# luca.net
KiCad netlist of a schematic drawn in EAGLE
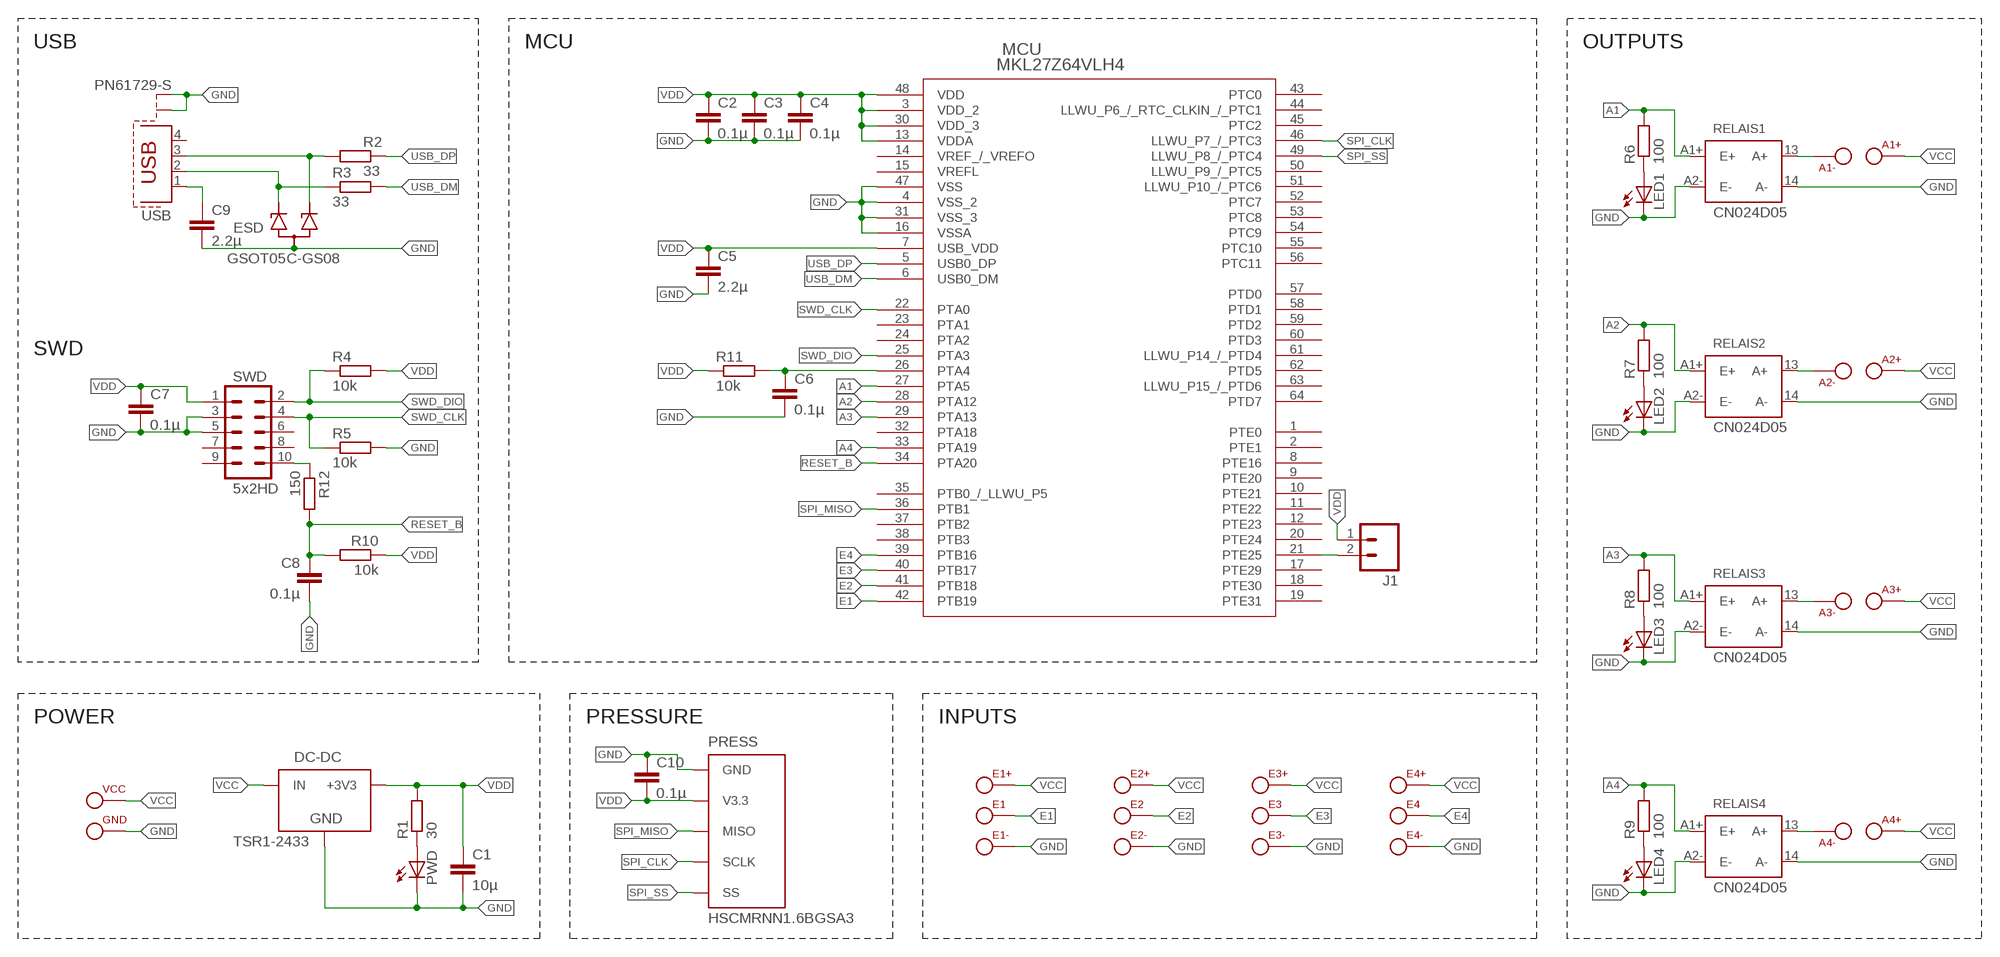
[diagram p0: schematic, sheet 1]

(export (version "E")
  (design (tool "Eeschema 10.0.6"))
  (components
    (comp (ref "A1+")
      (value "FFKDS-2,54")
      (footprint "eagle-import:FFSDK-2,54")
      (libsource (lib "eagle-import") (part "FFKDS-2,54"))
    )
    (comp (ref "A1-")
      (value "FFKDS-2,54")
      (footprint "eagle-import:FFSDK-2,54")
      (libsource (lib "eagle-import") (part "FFKDS-2,54"))
    )
    (comp (ref "A2+")
      (value "FFKDS-2,54")
      (footprint "eagle-import:FFSDK-2,54")
      (libsource (lib "eagle-import") (part "FFKDS-2,54"))
    )
    (comp (ref "A2-")
      (value "FFKDS-2,54")
      (footprint "eagle-import:FFSDK-2,54")
      (libsource (lib "eagle-import") (part "FFKDS-2,54"))
    )
    (comp (ref "A3+")
      (value "FFKDS-2,54")
      (footprint "eagle-import:FFSDK-2,54")
      (libsource (lib "eagle-import") (part "FFKDS-2,54"))
    )
    (comp (ref "A3-")
      (value "FFKDS-2,54")
      (footprint "eagle-import:FFSDK-2,54")
      (libsource (lib "eagle-import") (part "FFKDS-2,54"))
    )
    (comp (ref "A4+")
      (value "FFKDS-2,54")
      (footprint "eagle-import:FFSDK-2,54")
      (libsource (lib "eagle-import") (part "FFKDS-2,54"))
    )
    (comp (ref "A4-")
      (value "FFKDS-2,54")
      (footprint "eagle-import:FFSDK-2,54")
      (libsource (lib "eagle-import") (part "FFKDS-2,54"))
    )
    (comp (ref "C1")
      (value "10µ")
      (footprint "eagle-import:C1206")
      (libsource (lib "eagle-import") (part "C-EUC1206"))
    )
    (comp (ref "C2")
      (value "0.1µ")
      (footprint "eagle-import:C1206")
      (libsource (lib "eagle-import") (part "C-EUC1206"))
    )
    (comp (ref "C3")
      (value "0.1µ")
      (footprint "eagle-import:C1206")
      (libsource (lib "eagle-import") (part "C-EUC1206"))
    )
    (comp (ref "C4")
      (value "0.1µ")
      (footprint "eagle-import:C1206")
      (libsource (lib "eagle-import") (part "C-EUC1206"))
    )
    (comp (ref "C5")
      (value "2.2µ")
      (footprint "eagle-import:C1206")
      (libsource (lib "eagle-import") (part "C-EUC1206"))
    )
    (comp (ref "C6")
      (value "0.1µ")
      (footprint "eagle-import:C1206")
      (libsource (lib "eagle-import") (part "C-EUC1206"))
    )
    (comp (ref "C7")
      (value "0.1µ")
      (footprint "eagle-import:C1206")
      (libsource (lib "eagle-import") (part "C-EUC1206"))
    )
    (comp (ref "C8")
      (value "0.1µ")
      (footprint "eagle-import:C1206")
      (libsource (lib "eagle-import") (part "C-EUC1206"))
    )
    (comp (ref "C9")
      (value "2.2µ")
      (footprint "eagle-import:C1206")
      (libsource (lib "eagle-import") (part "C-EUC1206"))
    )
    (comp (ref "C10")
      (value "0.1µ")
      (footprint "eagle-import:C1206")
      (libsource (lib "eagle-import") (part "C-EUC1206"))
    )
    (comp (ref "DC-DC")
      (value "TSR1-2433")
      (footprint "eagle-import:TSR-1")
      (libsource (lib "eagle-import") (part "TSR1-2433"))
    )
    (comp (ref "E1")
      (value "FFKDS-2,54")
      (footprint "eagle-import:FFSDK-2,54")
      (libsource (lib "eagle-import") (part "FFKDS-2,54"))
    )
    (comp (ref "E1+")
      (value "FFKDS-2,54")
      (footprint "eagle-import:FFSDK-2,54")
      (libsource (lib "eagle-import") (part "FFKDS-2,54"))
    )
    (comp (ref "E1-")
      (value "FFKDS-2,54")
      (footprint "eagle-import:FFSDK-2,54")
      (libsource (lib "eagle-import") (part "FFKDS-2,54"))
    )
    (comp (ref "E2")
      (value "FFKDS-2,54")
      (footprint "eagle-import:FFSDK-2,54")
      (libsource (lib "eagle-import") (part "FFKDS-2,54"))
    )
    (comp (ref "E2+")
      (value "FFKDS-2,54")
      (footprint "eagle-import:FFSDK-2,54")
      (libsource (lib "eagle-import") (part "FFKDS-2,54"))
    )
    (comp (ref "E2-")
      (value "FFKDS-2,54")
      (footprint "eagle-import:FFSDK-2,54")
      (libsource (lib "eagle-import") (part "FFKDS-2,54"))
    )
    (comp (ref "E3")
      (value "FFKDS-2,54")
      (footprint "eagle-import:FFSDK-2,54")
      (libsource (lib "eagle-import") (part "FFKDS-2,54"))
    )
    (comp (ref "E3+")
      (value "FFKDS-2,54")
      (footprint "eagle-import:FFSDK-2,54")
      (libsource (lib "eagle-import") (part "FFKDS-2,54"))
    )
    (comp (ref "E3-")
      (value "FFKDS-2,54")
      (footprint "eagle-import:FFSDK-2,54")
      (libsource (lib "eagle-import") (part "FFKDS-2,54"))
    )
    (comp (ref "E4")
      (value "FFKDS-2,54")
      (footprint "eagle-import:FFSDK-2,54")
      (libsource (lib "eagle-import") (part "FFKDS-2,54"))
    )
    (comp (ref "E4+")
      (value "FFKDS-2,54")
      (footprint "eagle-import:FFSDK-2,54")
      (libsource (lib "eagle-import") (part "FFKDS-2,54"))
    )
    (comp (ref "E4-")
      (value "FFKDS-2,54")
      (footprint "eagle-import:FFSDK-2,54")
      (libsource (lib "eagle-import") (part "FFKDS-2,54"))
    )
    (comp (ref "ESD")
      (value "GSOT05C-GS08")
      (footprint "eagle-import:GSOT05C-GS08")
      (libsource (lib "eagle-import") (part "GSOT05C-GS08"))
    )
    (comp (ref "GND")
      (value "FFKDS-2,54")
      (footprint "eagle-import:FFSDK-2,54")
      (libsource (lib "eagle-import") (part "FFKDS-2,54"))
    )
    (comp (ref "J1")
      (value "M02LOCK")
      (footprint "eagle-import:1X02_LOCK")
      (libsource (lib "eagle-import") (part "M02LOCK"))
    )
    (comp (ref "LED1")
      (value "LED")
      (footprint "eagle-import:LED")
      (libsource (lib "eagle-import") (part "LED"))
    )
    (comp (ref "LED2")
      (value "LED")
      (footprint "eagle-import:LED")
      (libsource (lib "eagle-import") (part "LED"))
    )
    (comp (ref "LED3")
      (value "LED")
      (footprint "eagle-import:LED")
      (libsource (lib "eagle-import") (part "LED"))
    )
    (comp (ref "LED4")
      (value "LED")
      (footprint "eagle-import:LED")
      (libsource (lib "eagle-import") (part "LED"))
    )
    (comp (ref "MCU")
      (value "MKL27Z64VLH4")
      (footprint "eagle-import:98ASS23234W")
      (fields (field (name "MANUFACTURER_PART_NUMBER") "mkl27z64vlh4"))
      (libsource (lib "eagle-import") (part "MKL27Z64VLH4"))
    )
    (comp (ref "PRESS")
      (value "HSCMRNN1.6BGSA3")
      (footprint "eagle-import:HSCMRNN1.6BGSA3")
      (libsource (lib "eagle-import") (part "HSCMRNN1.6BGSA3"))
    )
    (comp (ref "PWD")
      (value "LED")
      (footprint "eagle-import:LED")
      (libsource (lib "eagle-import") (part "LED"))
    )
    (comp (ref "R1")
      (value "30")
      (footprint "eagle-import:M1206")
      (libsource (lib "eagle-import") (part "R-EU_M1206"))
    )
    (comp (ref "R2")
      (value "33")
      (footprint "eagle-import:M1206")
      (libsource (lib "eagle-import") (part "R-EU_M1206"))
    )
    (comp (ref "R3")
      (value "33")
      (footprint "eagle-import:M1206")
      (libsource (lib "eagle-import") (part "R-EU_M1206"))
    )
    (comp (ref "R4")
      (value "10k")
      (footprint "eagle-import:M1206")
      (libsource (lib "eagle-import") (part "R-EU_M1206"))
    )
    (comp (ref "R5")
      (value "10k")
      (footprint "eagle-import:M1206")
      (libsource (lib "eagle-import") (part "R-EU_M1206"))
    )
    (comp (ref "R6")
      (value "100")
      (footprint "eagle-import:M1206")
      (libsource (lib "eagle-import") (part "R-EU_M1206"))
    )
    (comp (ref "R7")
      (value "100")
      (footprint "eagle-import:M1206")
      (libsource (lib "eagle-import") (part "R-EU_M1206"))
    )
    (comp (ref "R8")
      (value "100")
      (footprint "eagle-import:M1206")
      (libsource (lib "eagle-import") (part "R-EU_M1206"))
    )
    (comp (ref "R9")
      (value "100")
      (footprint "eagle-import:M1206")
      (libsource (lib "eagle-import") (part "R-EU_M1206"))
    )
    (comp (ref "R10")
      (value "10k")
      (footprint "eagle-import:M1206")
      (libsource (lib "eagle-import") (part "R-EU_M1206"))
    )
    (comp (ref "R11")
      (value "10k")
      (footprint "eagle-import:M1206")
      (libsource (lib "eagle-import") (part "R-EU_M1206"))
    )
    (comp (ref "R12")
      (value "150")
      (footprint "eagle-import:M1206")
      (libsource (lib "eagle-import") (part "R-EU_M1206"))
    )
    (comp (ref "RELAIS1")
      (value "CN024D05")
      (footprint "eagle-import:CN024D05")
      (libsource (lib "eagle-import") (part "CN024D05"))
    )
    (comp (ref "RELAIS2")
      (value "CN024D05")
      (footprint "eagle-import:CN024D05")
      (libsource (lib "eagle-import") (part "CN024D05"))
    )
    (comp (ref "RELAIS3")
      (value "CN024D05")
      (footprint "eagle-import:CN024D05")
      (libsource (lib "eagle-import") (part "CN024D05"))
    )
    (comp (ref "RELAIS4")
      (value "CN024D05")
      (footprint "eagle-import:CN024D05")
      (libsource (lib "eagle-import") (part "CN024D05"))
    )
    (comp (ref "SWD")
      (value "5x2HD")
      (footprint "eagle-import:2X5-PTH-1.27MM")
      (libsource (lib "eagle-import") (part "M05X22X"))
    )
    (comp (ref "USB")
      (value "PN61729-S")
      (footprint "eagle-import:PN61729-S")
      (libsource (lib "eagle-import") (part "PN61729-S"))
    )
    (comp (ref "VCC")
      (value "FFKDS-2,54")
      (footprint "eagle-import:FFSDK-2,54")
      (libsource (lib "eagle-import") (part "FFKDS-2,54"))
    )
  )
  (nets
    (net (code "1") (name "/VREFL") (class "Default")
      (node (ref "MCU") (pin "15") (pinfunction "VREFL_15") (pintype "power_in"))
    )
    (net (code "2") (name "/VREF_{slash}_VREFO") (class "Default")
      (node (ref "MCU") (pin "14") (pinfunction "VREF_/_VREFO_14") (pintype "power_in"))
    )
    (net (code "3") (name "A1") (class "Default")
      (node (ref "MCU") (pin "27") (pinfunction "PTA5_27") (pintype "passive"))
      (node (ref "R6") (pin "2") (pinfunction "2_2") (pintype "passive"))
      (node (ref "RELAIS1") (pin "A1+") (pinfunction "E+_A1+") (pintype "bidirectional"))
    )
    (net (code "4") (name "A2") (class "Default")
      (node (ref "MCU") (pin "28") (pinfunction "PTA12_28") (pintype "passive"))
      (node (ref "R7") (pin "2") (pinfunction "2_2") (pintype "passive"))
      (node (ref "RELAIS2") (pin "A1+") (pinfunction "E+_A1+") (pintype "bidirectional"))
    )
    (net (code "5") (name "A3") (class "Default")
      (node (ref "MCU") (pin "29") (pinfunction "PTA13_29") (pintype "passive"))
      (node (ref "R8") (pin "2") (pinfunction "2_2") (pintype "passive"))
      (node (ref "RELAIS3") (pin "A1+") (pinfunction "E+_A1+") (pintype "bidirectional"))
    )
    (net (code "6") (name "A4") (class "Default")
      (node (ref "MCU") (pin "33") (pinfunction "PTA19_33") (pintype "passive"))
      (node (ref "R9") (pin "2") (pinfunction "2_2") (pintype "passive"))
      (node (ref "RELAIS4") (pin "A1+") (pinfunction "E+_A1+") (pintype "bidirectional"))
    )
    (net (code "7") (name "E1") (class "Default")
      (node (ref "E1") (pin "1") (pinfunction "P1_1") (pintype "bidirectional"))
      (node (ref "E1") (pin "2") (pinfunction "P1_2") (pintype "bidirectional"))
      (node (ref "MCU") (pin "42") (pinfunction "PTB19_42") (pintype "passive"))
    )
    (net (code "8") (name "E2") (class "Default")
      (node (ref "E2") (pin "1") (pinfunction "P1_1") (pintype "bidirectional"))
      (node (ref "E2") (pin "2") (pinfunction "P1_2") (pintype "bidirectional"))
      (node (ref "MCU") (pin "41") (pinfunction "PTB18_41") (pintype "passive"))
    )
    (net (code "9") (name "E3") (class "Default")
      (node (ref "E3") (pin "1") (pinfunction "P1_1") (pintype "bidirectional"))
      (node (ref "E3") (pin "2") (pinfunction "P1_2") (pintype "bidirectional"))
      (node (ref "MCU") (pin "40") (pinfunction "PTB17_40") (pintype "passive"))
    )
    (net (code "10") (name "E4") (class "Default")
      (node (ref "E4") (pin "1") (pinfunction "P1_1") (pintype "bidirectional"))
      (node (ref "E4") (pin "2") (pinfunction "P1_2") (pintype "bidirectional"))
      (node (ref "MCU") (pin "39") (pinfunction "PTB16_39") (pintype "passive"))
    )
    (net (code "11") (name "GND") (class "Default")
      (node (ref "C1") (pin "2") (pinfunction "2_2") (pintype "passive"))
      (node (ref "C10") (pin "1") (pinfunction "1_1") (pintype "passive"))
      (node (ref "C2") (pin "2") (pinfunction "2_2") (pintype "passive"))
      (node (ref "C3") (pin "2") (pinfunction "2_2") (pintype "passive"))
      (node (ref "C4") (pin "2") (pinfunction "2_2") (pintype "passive"))
      (node (ref "C5") (pin "2") (pinfunction "2_2") (pintype "passive"))
      (node (ref "C6") (pin "2") (pinfunction "2_2") (pintype "passive"))
      (node (ref "C7") (pin "2") (pinfunction "2_2") (pintype "passive"))
      (node (ref "C8") (pin "2") (pinfunction "2_2") (pintype "passive"))
      (node (ref "C9") (pin "2") (pinfunction "2_2") (pintype "passive"))
      (node (ref "DC-DC") (pin "2") (pinfunction "GND_2") (pintype "power_in"))
      (node (ref "E1-") (pin "1") (pinfunction "P1_1") (pintype "bidirectional"))
      (node (ref "E1-") (pin "2") (pinfunction "P1_2") (pintype "bidirectional"))
      (node (ref "E2-") (pin "1") (pinfunction "P1_1") (pintype "bidirectional"))
      (node (ref "E2-") (pin "2") (pinfunction "P1_2") (pintype "bidirectional"))
      (node (ref "E3-") (pin "1") (pinfunction "P1_1") (pintype "bidirectional"))
      (node (ref "E3-") (pin "2") (pinfunction "P1_2") (pintype "bidirectional"))
      (node (ref "E4-") (pin "1") (pinfunction "P1_1") (pintype "bidirectional"))
      (node (ref "E4-") (pin "2") (pinfunction "P1_2") (pintype "bidirectional"))
      (node (ref "ESD") (pin "P$3") (pinfunction "P$3_P$3") (pintype "bidirectional"))
      (node (ref "GND") (pin "1") (pinfunction "P1_1") (pintype "bidirectional"))
      (node (ref "GND") (pin "2") (pinfunction "P1_2") (pintype "bidirectional"))
      (node (ref "LED1") (pin "B") (pinfunction "C_B") (pintype "passive"))
      (node (ref "LED2") (pin "B") (pinfunction "C_B") (pintype "passive"))
      (node (ref "LED3") (pin "B") (pinfunction "C_B") (pintype "passive"))
      (node (ref "LED4") (pin "B") (pinfunction "C_B") (pintype "passive"))
      (node (ref "MCU") (pin "16") (pinfunction "VSSA_16") (pintype "power_in"))
      (node (ref "MCU") (pin "31") (pinfunction "VSS_3_31") (pintype "power_in"))
      (node (ref "MCU") (pin "4") (pinfunction "VSS_2_4") (pintype "power_in"))
      (node (ref "MCU") (pin "47") (pinfunction "VSS_47") (pintype "power_in"))
      (node (ref "PRESS") (pin "P$1") (pinfunction "GND_P$1") (pintype "bidirectional"))
      (node (ref "PWD") (pin "B") (pinfunction "C_B") (pintype "passive"))
      (node (ref "R5") (pin "2") (pinfunction "2_2") (pintype "passive"))
      (node (ref "RELAIS1") (pin "14") (pinfunction "A-_14") (pintype "bidirectional"))
      (node (ref "RELAIS1") (pin "A2-") (pinfunction "E-_A2-") (pintype "bidirectional"))
      (node (ref "RELAIS2") (pin "14") (pinfunction "A-_14") (pintype "bidirectional"))
      (node (ref "RELAIS2") (pin "A2-") (pinfunction "E-_A2-") (pintype "bidirectional"))
      (node (ref "RELAIS3") (pin "14") (pinfunction "A-_14") (pintype "bidirectional"))
      (node (ref "RELAIS3") (pin "A2-") (pinfunction "E-_A2-") (pintype "bidirectional"))
      (node (ref "RELAIS4") (pin "14") (pinfunction "A-_14") (pintype "bidirectional"))
      (node (ref "RELAIS4") (pin "A2-") (pinfunction "E-_A2-") (pintype "bidirectional"))
      (node (ref "SWD") (pin "3") (pinfunction "3_3") (pintype "passive"))
      (node (ref "SWD") (pin "5") (pinfunction "5_5") (pintype "passive"))
      (node (ref "USB") (pin "S1") (pinfunction "S1_S1") (pintype "passive"))
      (node (ref "USB") (pin "S2") (pinfunction "S2_S2") (pintype "passive"))
    )
    (net (code "12") (name "Net-(C9-Pad1)") (class "Default")
      (node (ref "C9") (pin "1") (pinfunction "1_1") (pintype "passive"))
      (node (ref "USB") (pin "1") (pinfunction "1_1") (pintype "passive"))
    )
    (net (code "13") (name "Net-(ESD-PadP$1)") (class "Default")
      (node (ref "ESD") (pin "P$1") (pinfunction "P$1_P$1") (pintype "bidirectional"))
      (node (ref "R2") (pin "1") (pinfunction "1_1") (pintype "passive"))
      (node (ref "USB") (pin "3") (pinfunction "3_3") (pintype "passive"))
    )
    (net (code "14") (name "Net-(ESD-PadP$2)") (class "Default")
      (node (ref "ESD") (pin "P$2") (pinfunction "P$2_P$2") (pintype "bidirectional"))
      (node (ref "R3") (pin "1") (pinfunction "1_1") (pintype "passive"))
      (node (ref "USB") (pin "2") (pinfunction "2_2") (pintype "passive"))
    )
    (net (code "15") (name "Net-(LED1-PadA)") (class "Default")
      (node (ref "LED1") (pin "A") (pinfunction "A_A") (pintype "passive"))
      (node (ref "R6") (pin "1") (pinfunction "1_1") (pintype "passive"))
    )
    (net (code "16") (name "Net-(LED2-PadA)") (class "Default")
      (node (ref "LED2") (pin "A") (pinfunction "A_A") (pintype "passive"))
      (node (ref "R7") (pin "1") (pinfunction "1_1") (pintype "passive"))
    )
    (net (code "17") (name "Net-(LED3-PadA)") (class "Default")
      (node (ref "LED3") (pin "A") (pinfunction "A_A") (pintype "passive"))
      (node (ref "R8") (pin "1") (pinfunction "1_1") (pintype "passive"))
    )
    (net (code "18") (name "Net-(LED4-PadA)") (class "Default")
      (node (ref "LED4") (pin "A") (pinfunction "A_A") (pintype "passive"))
      (node (ref "R9") (pin "1") (pinfunction "1_1") (pintype "passive"))
    )
    (net (code "19") (name "Net-(MCU-PTA4)") (class "Default")
      (node (ref "C6") (pin "1") (pinfunction "1_1") (pintype "passive"))
      (node (ref "MCU") (pin "26") (pinfunction "PTA4_26") (pintype "passive"))
      (node (ref "R11") (pin "2") (pinfunction "2_2") (pintype "passive"))
    )
    (net (code "20") (name "Net-(MCU-PTE25)") (class "Default")
      (node (ref "J1") (pin "2") (pinfunction "2_2") (pintype "passive"))
      (node (ref "MCU") (pin "21") (pinfunction "PTE25_21") (pintype "passive"))
    )
    (net (code "21") (name "Net-(PWD-PadA)") (class "Default")
      (node (ref "PWD") (pin "A") (pinfunction "A_A") (pintype "passive"))
      (node (ref "R1") (pin "1") (pinfunction "1_1") (pintype "passive"))
    )
    (net (code "22") (name "Net-(R12-Pad1)") (class "Default")
      (node (ref "R12") (pin "1") (pinfunction "1_1") (pintype "passive"))
      (node (ref "SWD") (pin "10") (pinfunction "10_10") (pintype "passive"))
    )
    (net (code "23") (name "Net-(RELAIS1-A+)") (class "Default")
      (node (ref "A1-") (pin "1") (pinfunction "P1_1") (pintype "bidirectional"))
      (node (ref "A1-") (pin "2") (pinfunction "P1_2") (pintype "bidirectional"))
      (node (ref "RELAIS1") (pin "13") (pinfunction "A+_13") (pintype "bidirectional"))
    )
    (net (code "24") (name "Net-(RELAIS2-A+)") (class "Default")
      (node (ref "A2-") (pin "1") (pinfunction "P1_1") (pintype "bidirectional"))
      (node (ref "A2-") (pin "2") (pinfunction "P1_2") (pintype "bidirectional"))
      (node (ref "RELAIS2") (pin "13") (pinfunction "A+_13") (pintype "bidirectional"))
    )
    (net (code "25") (name "Net-(RELAIS3-A+)") (class "Default")
      (node (ref "A3-") (pin "1") (pinfunction "P1_1") (pintype "bidirectional"))
      (node (ref "A3-") (pin "2") (pinfunction "P1_2") (pintype "bidirectional"))
      (node (ref "RELAIS3") (pin "13") (pinfunction "A+_13") (pintype "bidirectional"))
    )
    (net (code "26") (name "Net-(RELAIS4-A+)") (class "Default")
      (node (ref "A4-") (pin "1") (pinfunction "P1_1") (pintype "bidirectional"))
      (node (ref "A4-") (pin "2") (pinfunction "P1_2") (pintype "bidirectional"))
      (node (ref "RELAIS4") (pin "13") (pinfunction "A+_13") (pintype "bidirectional"))
    )
    (net (code "27") (name "RESET_B") (class "Default")
      (node (ref "C8") (pin "1") (pinfunction "1_1") (pintype "passive"))
      (node (ref "MCU") (pin "34") (pinfunction "PTA20_34") (pintype "passive"))
      (node (ref "R10") (pin "2") (pinfunction "2_2") (pintype "passive"))
      (node (ref "R12") (pin "2") (pinfunction "2_2") (pintype "passive"))
    )
    (net (code "28") (name "SPI_CLK") (class "Default")
      (node (ref "MCU") (pin "46") (pinfunction "LLWU_P7_/_PTC3_46") (pintype "passive"))
      (node (ref "PRESS") (pin "P$4") (pinfunction "SCLK_P$4") (pintype "bidirectional"))
    )
    (net (code "29") (name "SPI_MISO") (class "Default")
      (node (ref "MCU") (pin "36") (pinfunction "PTB1_36") (pintype "passive"))
      (node (ref "PRESS") (pin "P$3") (pinfunction "MISO_P$3") (pintype "bidirectional"))
    )
    (net (code "30") (name "SPI_SS") (class "Default")
      (node (ref "MCU") (pin "49") (pinfunction "LLWU_P8_/_PTC4_49") (pintype "passive"))
      (node (ref "PRESS") (pin "P$5") (pinfunction "SS_P$5") (pintype "bidirectional"))
    )
    (net (code "31") (name "SWD_CLK") (class "Default")
      (node (ref "MCU") (pin "22") (pinfunction "PTA0_22") (pintype "passive"))
      (node (ref "R5") (pin "1") (pinfunction "1_1") (pintype "passive"))
      (node (ref "SWD") (pin "4") (pinfunction "4_4") (pintype "passive"))
    )
    (net (code "32") (name "SWD_DIO") (class "Default")
      (node (ref "MCU") (pin "25") (pinfunction "PTA3_25") (pintype "passive"))
      (node (ref "R4") (pin "1") (pinfunction "1_1") (pintype "passive"))
      (node (ref "SWD") (pin "2") (pinfunction "2_2") (pintype "passive"))
    )
    (net (code "33") (name "USB_DM") (class "Default")
      (node (ref "MCU") (pin "6") (pinfunction "USB0_DM_6") (pintype "passive"))
      (node (ref "R3") (pin "2") (pinfunction "2_2") (pintype "passive"))
    )
    (net (code "34") (name "USB_DP") (class "Default")
      (node (ref "MCU") (pin "5") (pinfunction "USB0_DP_5") (pintype "passive"))
      (node (ref "R2") (pin "2") (pinfunction "2_2") (pintype "passive"))
    )
    (net (code "35") (name "VCC") (class "Default")
      (node (ref "A1+") (pin "1") (pinfunction "P1_1") (pintype "bidirectional"))
      (node (ref "A1+") (pin "2") (pinfunction "P1_2") (pintype "bidirectional"))
      (node (ref "A2+") (pin "1") (pinfunction "P1_1") (pintype "bidirectional"))
      (node (ref "A2+") (pin "2") (pinfunction "P1_2") (pintype "bidirectional"))
      (node (ref "A3+") (pin "1") (pinfunction "P1_1") (pintype "bidirectional"))
      (node (ref "A3+") (pin "2") (pinfunction "P1_2") (pintype "bidirectional"))
      (node (ref "A4+") (pin "1") (pinfunction "P1_1") (pintype "bidirectional"))
      (node (ref "A4+") (pin "2") (pinfunction "P1_2") (pintype "bidirectional"))
      (node (ref "DC-DC") (pin "1") (pinfunction "IN_1") (pintype "power_in"))
      (node (ref "E1+") (pin "1") (pinfunction "P1_1") (pintype "bidirectional"))
      (node (ref "E1+") (pin "2") (pinfunction "P1_2") (pintype "bidirectional"))
      (node (ref "E2+") (pin "1") (pinfunction "P1_1") (pintype "bidirectional"))
      (node (ref "E2+") (pin "2") (pinfunction "P1_2") (pintype "bidirectional"))
      (node (ref "E3+") (pin "1") (pinfunction "P1_1") (pintype "bidirectional"))
      (node (ref "E3+") (pin "2") (pinfunction "P1_2") (pintype "bidirectional"))
      (node (ref "E4+") (pin "1") (pinfunction "P1_1") (pintype "bidirectional"))
      (node (ref "E4+") (pin "2") (pinfunction "P1_2") (pintype "bidirectional"))
      (node (ref "VCC") (pin "1") (pinfunction "P1_1") (pintype "bidirectional"))
      (node (ref "VCC") (pin "2") (pinfunction "P1_2") (pintype "bidirectional"))
    )
    (net (code "36") (name "VDD") (class "Default")
      (node (ref "C1") (pin "1") (pinfunction "1_1") (pintype "passive"))
      (node (ref "C10") (pin "2") (pinfunction "2_2") (pintype "passive"))
      (node (ref "C2") (pin "1") (pinfunction "1_1") (pintype "passive"))
      (node (ref "C3") (pin "1") (pinfunction "1_1") (pintype "passive"))
      (node (ref "C4") (pin "1") (pinfunction "1_1") (pintype "passive"))
      (node (ref "C5") (pin "1") (pinfunction "1_1") (pintype "passive"))
      (node (ref "C7") (pin "1") (pinfunction "1_1") (pintype "passive"))
      (node (ref "DC-DC") (pin "3") (pinfunction "+3V3_3") (pintype "power_in"))
      (node (ref "J1") (pin "1") (pinfunction "1_1") (pintype "passive"))
      (node (ref "MCU") (pin "13") (pinfunction "VDDA_13") (pintype "power_in"))
      (node (ref "MCU") (pin "3") (pinfunction "VDD_2_3") (pintype "power_in"))
      (node (ref "MCU") (pin "30") (pinfunction "VDD_3_30") (pintype "power_in"))
      (node (ref "MCU") (pin "48") (pinfunction "VDD_48") (pintype "power_in"))
      (node (ref "MCU") (pin "7") (pinfunction "USB_VDD_7") (pintype "power_in"))
      (node (ref "PRESS") (pin "P$2") (pinfunction "V3.3_P$2") (pintype "bidirectional"))
      (node (ref "R1") (pin "2") (pinfunction "2_2") (pintype "passive"))
      (node (ref "R10") (pin "1") (pinfunction "1_1") (pintype "passive"))
      (node (ref "R11") (pin "1") (pinfunction "1_1") (pintype "passive"))
      (node (ref "R4") (pin "2") (pinfunction "2_2") (pintype "passive"))
      (node (ref "SWD") (pin "1") (pinfunction "1_1") (pintype "passive"))
    )
    (net (code "37") (name "unconnected-(MCU-LLWU_P6_{slash}_RTC_CLKIN_{slash}_PTC1-Pad44)") (class "Default")
      (node (ref "MCU") (pin "44") (pinfunction "LLWU_P6_/_RTC_CLKIN_/_PTC1_44") (pintype "passive"))
    )
    (net (code "38") (name "unconnected-(MCU-LLWU_P9_{slash}_PTC5-Pad50)") (class "Default")
      (node (ref "MCU") (pin "50") (pinfunction "LLWU_P9_/_PTC5_50") (pintype "passive"))
    )
    (net (code "39") (name "unconnected-(MCU-LLWU_P10_{slash}_PTC6-Pad51)") (class "Default")
      (node (ref "MCU") (pin "51") (pinfunction "LLWU_P10_/_PTC6_51") (pintype "passive"))
    )
    (net (code "40") (name "unconnected-(MCU-LLWU_P14_{slash}_PTD4-Pad61)") (class "Default")
      (node (ref "MCU") (pin "61") (pinfunction "LLWU_P14_/_PTD4_61") (pintype "passive"))
    )
    (net (code "41") (name "unconnected-(MCU-LLWU_P15_{slash}_PTD6-Pad63)") (class "Default")
      (node (ref "MCU") (pin "63") (pinfunction "LLWU_P15_/_PTD6_63") (pintype "passive"))
    )
    (net (code "42") (name "unconnected-(MCU-PTA1-Pad23)") (class "Default")
      (node (ref "MCU") (pin "23") (pinfunction "PTA1_23") (pintype "passive"))
    )
    (net (code "43") (name "unconnected-(MCU-PTA2-Pad24)") (class "Default")
      (node (ref "MCU") (pin "24") (pinfunction "PTA2_24") (pintype "passive"))
    )
    (net (code "44") (name "unconnected-(MCU-PTA18-Pad32)") (class "Default")
      (node (ref "MCU") (pin "32") (pinfunction "PTA18_32") (pintype "passive"))
    )
    (net (code "45") (name "unconnected-(MCU-PTB0_{slash}_LLWU_P5-Pad35)") (class "Default")
      (node (ref "MCU") (pin "35") (pinfunction "PTB0_/_LLWU_P5_35") (pintype "passive"))
    )
    (net (code "46") (name "unconnected-(MCU-PTB2-Pad37)") (class "Default")
      (node (ref "MCU") (pin "37") (pinfunction "PTB2_37") (pintype "passive"))
    )
    (net (code "47") (name "unconnected-(MCU-PTB3-Pad38)") (class "Default")
      (node (ref "MCU") (pin "38") (pinfunction "PTB3_38") (pintype "passive"))
    )
    (net (code "48") (name "unconnected-(MCU-PTC0-Pad43)") (class "Default")
      (node (ref "MCU") (pin "43") (pinfunction "PTC0_43") (pintype "passive"))
    )
    (net (code "49") (name "unconnected-(MCU-PTC2-Pad45)") (class "Default")
      (node (ref "MCU") (pin "45") (pinfunction "PTC2_45") (pintype "passive"))
    )
    (net (code "50") (name "unconnected-(MCU-PTC7-Pad52)") (class "Default")
      (node (ref "MCU") (pin "52") (pinfunction "PTC7_52") (pintype "passive"))
    )
    (net (code "51") (name "unconnected-(MCU-PTC8-Pad53)") (class "Default")
      (node (ref "MCU") (pin "53") (pinfunction "PTC8_53") (pintype "passive"))
    )
    (net (code "52") (name "unconnected-(MCU-PTC9-Pad54)") (class "Default")
      (node (ref "MCU") (pin "54") (pinfunction "PTC9_54") (pintype "passive"))
    )
    (net (code "53") (name "unconnected-(MCU-PTC10-Pad55)") (class "Default")
      (node (ref "MCU") (pin "55") (pinfunction "PTC10_55") (pintype "passive"))
    )
    (net (code "54") (name "unconnected-(MCU-PTC11-Pad56)") (class "Default")
      (node (ref "MCU") (pin "56") (pinfunction "PTC11_56") (pintype "passive"))
    )
    (net (code "55") (name "unconnected-(MCU-PTD0-Pad57)") (class "Default")
      (node (ref "MCU") (pin "57") (pinfunction "PTD0_57") (pintype "passive"))
    )
    (net (code "56") (name "unconnected-(MCU-PTD1-Pad58)") (class "Default")
      (node (ref "MCU") (pin "58") (pinfunction "PTD1_58") (pintype "passive"))
    )
    (net (code "57") (name "unconnected-(MCU-PTD2-Pad59)") (class "Default")
      (node (ref "MCU") (pin "59") (pinfunction "PTD2_59") (pintype "passive"))
    )
    (net (code "58") (name "unconnected-(MCU-PTD3-Pad60)") (class "Default")
      (node (ref "MCU") (pin "60") (pinfunction "PTD3_60") (pintype "passive"))
    )
    (net (code "59") (name "unconnected-(MCU-PTD5-Pad62)") (class "Default")
      (node (ref "MCU") (pin "62") (pinfunction "PTD5_62") (pintype "passive"))
    )
    (net (code "60") (name "unconnected-(MCU-PTD7-Pad64)") (class "Default")
      (node (ref "MCU") (pin "64") (pinfunction "PTD7_64") (pintype "passive"))
    )
    (net (code "61") (name "unconnected-(MCU-PTE0-Pad1)") (class "Default")
      (node (ref "MCU") (pin "1") (pinfunction "PTE0_1") (pintype "passive"))
    )
    (net (code "62") (name "unconnected-(MCU-PTE1-Pad2)") (class "Default")
      (node (ref "MCU") (pin "2") (pinfunction "PTE1_2") (pintype "passive"))
    )
    (net (code "63") (name "unconnected-(MCU-PTE16-Pad8)") (class "Default")
      (node (ref "MCU") (pin "8") (pinfunction "PTE16_8") (pintype "passive"))
    )
    (net (code "64") (name "unconnected-(MCU-PTE20-Pad9)") (class "Default")
      (node (ref "MCU") (pin "9") (pinfunction "PTE20_9") (pintype "passive"))
    )
    (net (code "65") (name "unconnected-(MCU-PTE21-Pad10)") (class "Default")
      (node (ref "MCU") (pin "10") (pinfunction "PTE21_10") (pintype "passive"))
    )
    (net (code "66") (name "unconnected-(MCU-PTE22-Pad11)") (class "Default")
      (node (ref "MCU") (pin "11") (pinfunction "PTE22_11") (pintype "passive"))
    )
    (net (code "67") (name "unconnected-(MCU-PTE23-Pad12)") (class "Default")
      (node (ref "MCU") (pin "12") (pinfunction "PTE23_12") (pintype "passive"))
    )
    (net (code "68") (name "unconnected-(MCU-PTE24-Pad20)") (class "Default")
      (node (ref "MCU") (pin "20") (pinfunction "PTE24_20") (pintype "passive"))
    )
    (net (code "69") (name "unconnected-(MCU-PTE29-Pad17)") (class "Default")
      (node (ref "MCU") (pin "17") (pinfunction "PTE29_17") (pintype "passive"))
    )
    (net (code "70") (name "unconnected-(MCU-PTE30-Pad18)") (class "Default")
      (node (ref "MCU") (pin "18") (pinfunction "PTE30_18") (pintype "passive"))
    )
    (net (code "71") (name "unconnected-(MCU-PTE31-Pad19)") (class "Default")
      (node (ref "MCU") (pin "19") (pinfunction "PTE31_19") (pintype "passive"))
    )
    (net (code "72") (name "unconnected-(SWD-Pad6)") (class "Default")
      (node (ref "SWD") (pin "6") (pinfunction "6_6") (pintype "passive"))
    )
    (net (code "73") (name "unconnected-(SWD-Pad7)") (class "Default")
      (node (ref "SWD") (pin "7") (pinfunction "7_7") (pintype "passive"))
    )
    (net (code "74") (name "unconnected-(SWD-Pad8)") (class "Default")
      (node (ref "SWD") (pin "8") (pinfunction "8_8") (pintype "passive"))
    )
    (net (code "75") (name "unconnected-(SWD-Pad9)") (class "Default")
      (node (ref "SWD") (pin "9") (pinfunction "9_9") (pintype "passive"))
    )
    (net (code "76") (name "unconnected-(USB-Pad4)") (class "Default")
      (node (ref "USB") (pin "4") (pinfunction "4_4") (pintype "passive"))
    )
  )
)
